# op-synth_0_83_bigger_mounting_holes.net
KiCad netlist of a schematic drawn in EAGLE
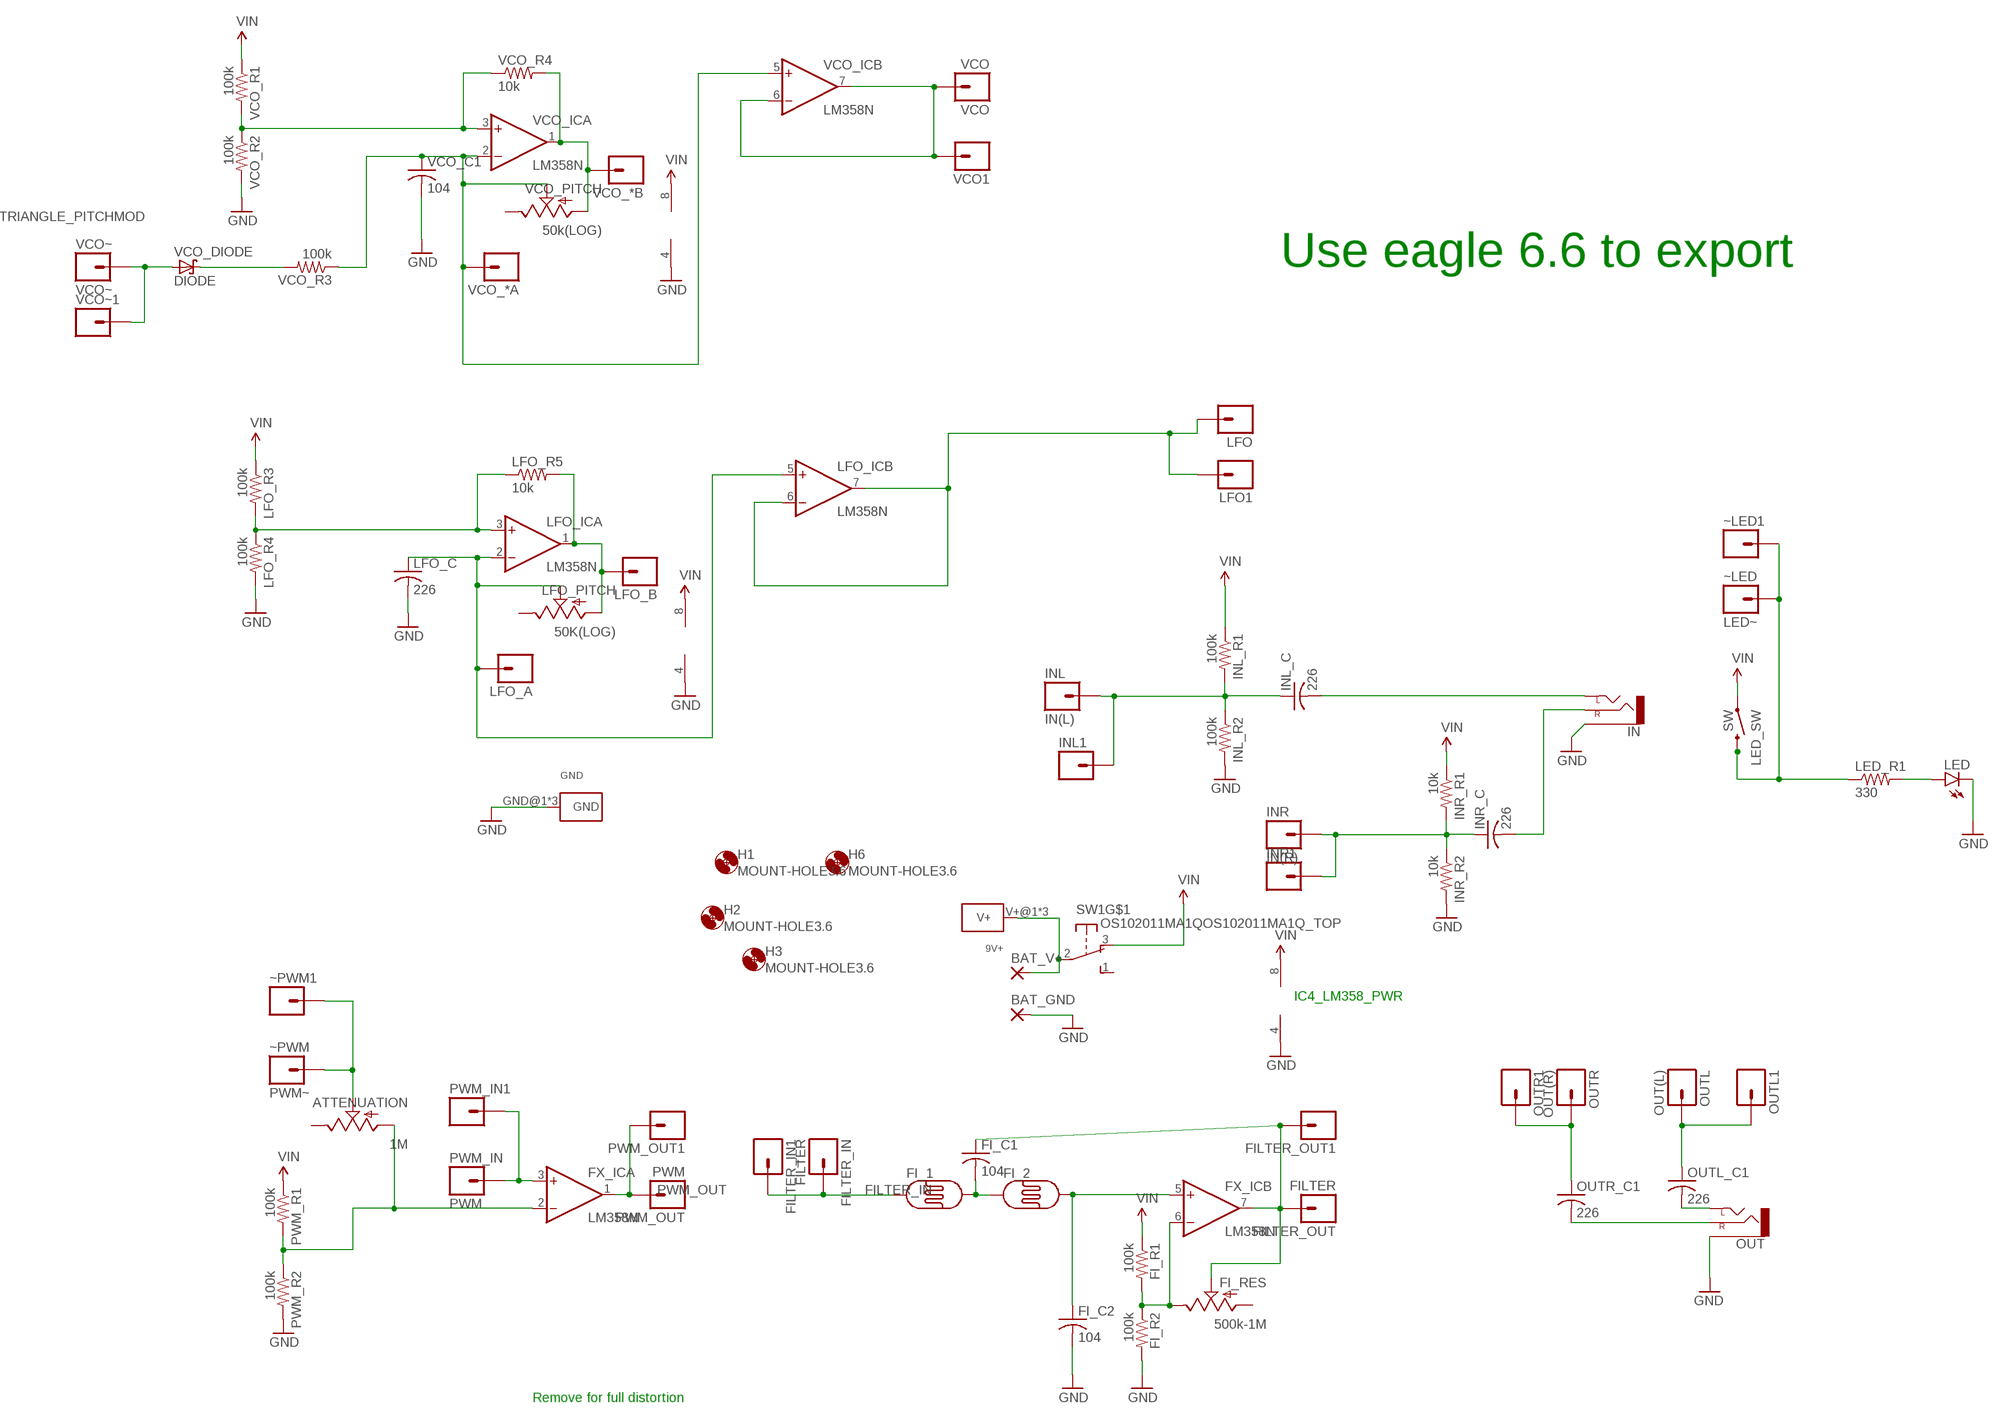
[diagram p0: schematic, sheet 1]

(export (version "E")
  (design (tool "Eeschema 10.0.6"))
  (components
    (comp (ref "9V+")
      (value "KEYSTONE-629+")
      (footprint "eagle-import:KEYSTONE_BATTAERY_TERMINAL-629+")
      (libsource (lib "eagle-import") (part "KEYSTONE-629+"))
    )
    (comp (ref "ATTENUATION")
      (value "1M")
      (footprint "eagle-import:TRIM_POT")
      (libsource (lib "eagle-import") (part "POTTRIM"))
    )
    (comp (ref "BAT_GND")
      (value "3,81/1,4")
      (footprint "eagle-import:3,81_1,4")
      (libsource (lib "eagle-import") (part "3,81/1,4"))
    )
    (comp (ref "BAT_V+")
      (value "3,81/1,4")
      (footprint "eagle-import:3,81_1,4")
      (libsource (lib "eagle-import") (part "3,81/1,4"))
    )
    (comp (ref "FILTER_IN")
      (value "FILTER")
      (footprint "eagle-import:1X01_SIDE_NAME")
      (libsource (lib "eagle-import") (part "HEADER-1X1"))
    )
    (comp (ref "FILTER_IN1")
      (value "HEADER-1X1")
      (footprint "eagle-import:1X01_SIDE_NAME")
      (libsource (lib "eagle-import") (part "HEADER-1X1"))
    )
    (comp (ref "FILTER_OUT")
      (value "FILTER")
      (footprint "eagle-import:1X01_SIDE_NAME")
      (libsource (lib "eagle-import") (part "HEADER-1X1"))
    )
    (comp (ref "FILTER_OUT1")
      (value "HEADER-1X1")
      (footprint "eagle-import:1X01_SIDE_NAME")
      (libsource (lib "eagle-import") (part "HEADER-1X1"))
    )
    (comp (ref "FI_1")
      (value "PHOTOCELLPTH")
      (footprint "eagle-import:PHOTOCELL")
      (libsource (lib "eagle-import") (part "PHOTOCELLPTH"))
    )
    (comp (ref "FI_2")
      (value "PHOTOCELLPTH")
      (footprint "eagle-import:PHOTOCELL")
      (libsource (lib "eagle-import") (part "PHOTOCELLPTH"))
    )
    (comp (ref "FI_C1")
      (value "104")
      (footprint "eagle-import:C050-024X044")
      (libsource (lib "eagle-import") (part "resistor_C-US050-024X044"))
    )
    (comp (ref "FI_C2")
      (value "104")
      (footprint "eagle-import:C050-024X044")
      (libsource (lib "eagle-import") (part "resistor_C-US050-024X044"))
    )
    (comp (ref "FI_R1")
      (value "100k")
      (footprint "eagle-import:0204_7")
      (libsource (lib "eagle-import") (part "R-US_0204/7"))
    )
    (comp (ref "FI_R2")
      (value "100k")
      (footprint "eagle-import:0204_7")
      (libsource (lib "eagle-import") (part "R-US_0204/7"))
    )
    (comp (ref "FI_RES")
      (value "500k-1M")
      (footprint "eagle-import:ALPS_POT")
      (libsource (lib "eagle-import") (part "POT"))
    )
    (comp (ref "FX_IC")
      (value "LM358N")
      (footprint "eagle-import:DIL08")
      (libsource (lib "eagle-import") (part "LM358N"))
    )
    (comp (ref "GND")
      (value "KEYSTONE-629")
      (footprint "eagle-import:KEYSTONE_AA_AAA_BATTERY_TERMINAL-629")
      (libsource (lib "eagle-import") (part "KEYSTONE-629"))
    )
    (comp (ref "H1")
      (value "MOUNT-HOLE3.6")
      (footprint "eagle-import:3,6")
      (libsource (lib "eagle-import") (part "MOUNT-HOLE3.6"))
    )
    (comp (ref "H2")
      (value "MOUNT-HOLE3.6")
      (footprint "eagle-import:3,6")
      (libsource (lib "eagle-import") (part "MOUNT-HOLE3.6"))
    )
    (comp (ref "H3")
      (value "MOUNT-HOLE3.6")
      (footprint "eagle-import:3,6")
      (libsource (lib "eagle-import") (part "MOUNT-HOLE3.6"))
    )
    (comp (ref "H6")
      (value "MOUNT-HOLE3.6")
      (footprint "eagle-import:3,6")
      (libsource (lib "eagle-import") (part "MOUNT-HOLE3.6"))
    )
    (comp (ref "IN")
      (value "AUDIO-JACKPTH")
      (footprint "eagle-import:AUDIO-JACK")
      (libsource (lib "eagle-import") (part "AUDIO-JACKPTH"))
    )
    (comp (ref "INL")
      (value "IN(L)")
      (footprint "eagle-import:1X01_SIDE_NAME")
      (libsource (lib "eagle-import") (part "HEADER-1X1"))
    )
    (comp (ref "INL1")
      (value "HEADER-1X1")
      (footprint "eagle-import:1X01_SIDE_NAME")
      (libsource (lib "eagle-import") (part "HEADER-1X1"))
    )
    (comp (ref "INL_C")
      (value "226")
      (footprint "eagle-import:C050-024X044")
      (libsource (lib "eagle-import") (part "C-US050-024X044"))
    )
    (comp (ref "INL_R1")
      (value "100k")
      (footprint "eagle-import:0204_7")
      (libsource (lib "eagle-import") (part "R-US_0204/7"))
    )
    (comp (ref "INL_R2")
      (value "100k")
      (footprint "eagle-import:0204_7")
      (libsource (lib "eagle-import") (part "R-US_0204/7"))
    )
    (comp (ref "INR")
      (value "IN(R)")
      (footprint "eagle-import:1X01_SIDE_NAME")
      (libsource (lib "eagle-import") (part "HEADER-1X1"))
    )
    (comp (ref "INR1")
      (value "HEADER-1X1")
      (footprint "eagle-import:1X01_SIDE_NAME")
      (libsource (lib "eagle-import") (part "HEADER-1X1"))
    )
    (comp (ref "INR_C")
      (value "226")
      (footprint "eagle-import:C050-024X044")
      (libsource (lib "eagle-import") (part "C-US050-024X044"))
    )
    (comp (ref "INR_R1")
      (value "10k")
      (footprint "eagle-import:0204_7")
      (libsource (lib "eagle-import") (part "R-US_0204/7"))
    )
    (comp (ref "INR_R2")
      (value "10k")
      (footprint "eagle-import:0204_7")
      (libsource (lib "eagle-import") (part "R-US_0204/7"))
    )
    (comp (ref "LED")
      (value "LED5MM")
      (footprint "eagle-import:LED5MM")
      (libsource (lib "eagle-import") (part "LED5MM"))
    )
    (comp (ref "LED_R1")
      (value "330")
      (footprint "eagle-import:0204_7")
      (libsource (lib "eagle-import") (part "R-US_0204/7"))
    )
    (comp (ref "LED_SW")
      (value "SW")
      (footprint "eagle-import:TACTILE-PTH-12MM")
      (libsource (lib "eagle-import") (part "SWITCH-MOMENTARY-212MM"))
    )
    (comp (ref "LFO")
      (value "HEADER-1X1")
      (footprint "eagle-import:1X01_SIDE_NAME")
      (libsource (lib "eagle-import") (part "HEADER-1X1"))
    )
    (comp (ref "LFO1")
      (value "HEADER-1X1")
      (footprint "eagle-import:1X01_SIDE_NAME")
      (libsource (lib "eagle-import") (part "HEADER-1X1"))
    )
    (comp (ref "LFO_A")
      (value "HEADER-1X1")
      (footprint "eagle-import:1X01_SIDE_NAME")
      (libsource (lib "eagle-import") (part "HEADER-1X1"))
    )
    (comp (ref "LFO_B")
      (value "HEADER-1X1")
      (footprint "eagle-import:1X01_SIDE_NAME")
      (libsource (lib "eagle-import") (part "HEADER-1X1"))
    )
    (comp (ref "LFO_C")
      (value "226")
      (footprint "eagle-import:C050-024X044")
      (libsource (lib "eagle-import") (part "resistor_C-US050-024X044"))
    )
    (comp (ref "LFO_IC")
      (value "LM358N")
      (footprint "eagle-import:DIL08")
      (libsource (lib "eagle-import") (part "LM358N"))
    )
    (comp (ref "LFO_PITCH")
      (value "50K(LOG)")
      (footprint "eagle-import:ALPS_POT")
      (libsource (lib "eagle-import") (part "POT"))
    )
    (comp (ref "LFO_R3")
      (value "100k")
      (footprint "eagle-import:0204_7")
      (libsource (lib "eagle-import") (part "R-US_0204/7"))
    )
    (comp (ref "LFO_R4")
      (value "100k")
      (footprint "eagle-import:0204_7")
      (libsource (lib "eagle-import") (part "R-US_0204/7"))
    )
    (comp (ref "LFO_R5")
      (value "10k")
      (footprint "eagle-import:0204_7")
      (libsource (lib "eagle-import") (part "R-US_0204/7"))
    )
    (comp (ref "OUT")
      (value "AUDIO-JACKPTH")
      (footprint "eagle-import:AUDIO-JACK")
      (libsource (lib "eagle-import") (part "AUDIO-JACKPTH"))
    )
    (comp (ref "OUTL")
      (value "OUT(L)")
      (footprint "eagle-import:1X01_SIDE_NAME")
      (libsource (lib "eagle-import") (part "HEADER-1X1"))
    )
    (comp (ref "OUTL1")
      (value "HEADER-1X1")
      (footprint "eagle-import:1X01_SIDE_NAME")
      (libsource (lib "eagle-import") (part "HEADER-1X1"))
    )
    (comp (ref "OUTL_C1")
      (value "226")
      (footprint "eagle-import:C050-024X044")
      (libsource (lib "eagle-import") (part "C-US050-024X044"))
    )
    (comp (ref "OUTR")
      (value "OUT(R)")
      (footprint "eagle-import:1X01_SIDE_NAME")
      (libsource (lib "eagle-import") (part "HEADER-1X1"))
    )
    (comp (ref "OUTR1")
      (value "HEADER-1X1")
      (footprint "eagle-import:1X01_SIDE_NAME")
      (libsource (lib "eagle-import") (part "HEADER-1X1"))
    )
    (comp (ref "OUTR_C1")
      (value "226")
      (footprint "eagle-import:C050-024X044")
      (libsource (lib "eagle-import") (part "C-US050-024X044"))
    )
    (comp (ref "PWM_IN")
      (value "PWM")
      (footprint "eagle-import:1X01_SIDE_NAME")
      (libsource (lib "eagle-import") (part "HEADER-1X1"))
    )
    (comp (ref "PWM_IN1")
      (value "HEADER-1X1")
      (footprint "eagle-import:1X01_SIDE_NAME")
      (libsource (lib "eagle-import") (part "HEADER-1X1"))
    )
    (comp (ref "PWM_OUT")
      (value "PWM")
      (footprint "eagle-import:1X01_SIDE_NAME")
      (libsource (lib "eagle-import") (part "HEADER-1X1"))
    )
    (comp (ref "PWM_OUT1")
      (value "HEADER-1X1")
      (footprint "eagle-import:1X01_SIDE_NAME")
      (libsource (lib "eagle-import") (part "HEADER-1X1"))
    )
    (comp (ref "PWM_R1")
      (value "100k")
      (footprint "eagle-import:0204_7")
      (libsource (lib "eagle-import") (part "R-US_0204/7"))
    )
    (comp (ref "PWM_R2")
      (value "100k")
      (footprint "eagle-import:0204_7")
      (libsource (lib "eagle-import") (part "R-US_0204/7"))
    )
    (comp (ref "SW1")
      (value "OS102011MA1QOS102011MA1Q_TOP")
      (footprint "eagle-import:OS102011MA1Q")
      (libsource (lib "eagle-import") (part "OS102011MA1QOS102011MA1Q_TOP"))
    )
    (comp (ref "VCO")
      (value "VCO")
      (footprint "eagle-import:1X01_SIDE_NAME")
      (libsource (lib "eagle-import") (part "HEADER-1X1"))
    )
    (comp (ref "VCO1")
      (value "HEADER-1X1")
      (footprint "eagle-import:1X01_SIDE_NAME")
      (libsource (lib "eagle-import") (part "HEADER-1X1"))
    )
    (comp (ref "VCO_*A")
      (value "HEADER-1X1")
      (footprint "eagle-import:1X01_SIDE_NAME")
      (libsource (lib "eagle-import") (part "HEADER-1X1"))
    )
    (comp (ref "VCO_*B")
      (value "HEADER-1X1")
      (footprint "eagle-import:1X01_SIDE_NAME")
      (libsource (lib "eagle-import") (part "HEADER-1X1"))
    )
    (comp (ref "VCO_C1")
      (value "104")
      (footprint "eagle-import:C050-024X044")
      (libsource (lib "eagle-import") (part "C-US050-024X044"))
    )
    (comp (ref "VCO_DIODE")
      (value "DIODE")
      (footprint "eagle-import:DO41-7")
      (libsource (lib "eagle-import") (part "SCHOTTKY-DIODEDO41-7"))
    )
    (comp (ref "VCO_IC")
      (value "LM358N")
      (footprint "eagle-import:DIL08")
      (libsource (lib "eagle-import") (part "LM358N"))
    )
    (comp (ref "VCO_PITCH")
      (value "50k(LOG)")
      (footprint "eagle-import:ALPS_POT")
      (libsource (lib "eagle-import") (part "POT"))
    )
    (comp (ref "VCO_R1")
      (value "100k")
      (footprint "eagle-import:0204_7")
      (libsource (lib "eagle-import") (part "R-US_0204/7"))
    )
    (comp (ref "VCO_R2")
      (value "100k")
      (footprint "eagle-import:0204_7")
      (libsource (lib "eagle-import") (part "R-US_0204/7"))
    )
    (comp (ref "VCO_R3")
      (value "100k")
      (footprint "eagle-import:0204_7")
      (libsource (lib "eagle-import") (part "R-US_0204/7"))
    )
    (comp (ref "VCO_R4")
      (value "10k")
      (footprint "eagle-import:0204_7")
      (libsource (lib "eagle-import") (part "R-US_0204/7"))
    )
    (comp (ref "VCO~")
      (value "VCO~")
      (footprint "eagle-import:1X01_SIDE_NAME")
      (libsource (lib "eagle-import") (part "HEADER-1X1"))
    )
    (comp (ref "VCO~1")
      (value "HEADER-1X1")
      (footprint "eagle-import:1X01_SIDE_NAME")
      (libsource (lib "eagle-import") (part "HEADER-1X1"))
    )
    (comp (ref "~LED")
      (value "LED~")
      (footprint "eagle-import:1X01_SIDE_NAME")
      (libsource (lib "eagle-import") (part "HEADER-1X1"))
    )
    (comp (ref "~LED1")
      (value "HEADER-1X1")
      (footprint "eagle-import:1X01_SIDE_NAME")
      (libsource (lib "eagle-import") (part "HEADER-1X1"))
    )
    (comp (ref "~PWM")
      (value "PWM~")
      (footprint "eagle-import:1X01_SIDE_NAME")
      (libsource (lib "eagle-import") (part "HEADER-1X1"))
    )
    (comp (ref "~PWM1")
      (value "HEADER-1X1")
      (footprint "eagle-import:1X01_SIDE_NAME")
      (libsource (lib "eagle-import") (part "HEADER-1X1"))
    )
  )
  (nets
    (net (code "1") (name "/FILTER_IN") (class "Default")
      (node (ref "FILTER_IN") (pin "1") (pinfunction "1_1") (pintype "passive"))
      (node (ref "FILTER_IN1") (pin "1") (pinfunction "1_1") (pintype "passive"))
      (node (ref "FI_1") (pin "1") (pinfunction "P$1_1") (pintype "bidirectional"))
    )
    (net (code "2") (name "/PWM_OUT") (class "Default")
      (node (ref "FX_IC") (pin "1") (pinfunction "OUT_1") (pintype "output"))
      (node (ref "PWM_OUT") (pin "1") (pinfunction "1_1") (pintype "passive"))
      (node (ref "PWM_OUT1") (pin "1") (pinfunction "1_1") (pintype "passive"))
    )
    (net (code "3") (name "/TRIANGLE_PITCHMOD") (class "Default")
      (node (ref "VCO_DIODE") (pin "A") (pinfunction "A_A") (pintype "passive"))
      (node (ref "VCO~") (pin "1") (pinfunction "1_1") (pintype "passive"))
      (node (ref "VCO~1") (pin "1") (pinfunction "1_1") (pintype "passive"))
    )
    (net (code "4") (name "GND") (class "Default")
      (node (ref "BAT_GND") (pin "1") (pinfunction "P_1") (pintype "passive"))
      (node (ref "FI_C2") (pin "2") (pinfunction "2_2") (pintype "passive"))
      (node (ref "FI_R2") (pin "2") (pinfunction "2_2") (pintype "passive"))
      (node (ref "FX_IC") (pin "4") (pinfunction "V-_4") (pintype "power_in"))
      (node (ref "GND") (pin "GND@1") (pinfunction "GND_GND@1") (pintype "power_in"))
      (node (ref "GND") (pin "GND@2") (pinfunction "GND_GND@2") (pintype "power_in"))
      (node (ref "GND") (pin "GND@3") (pinfunction "GND_GND@3") (pintype "power_in"))
      (node (ref "IN") (pin "SLEEVE") (pinfunction "SLEEVE_SLEEVE") (pintype "bidirectional"))
      (node (ref "INL_R2") (pin "2") (pinfunction "2_2") (pintype "passive"))
      (node (ref "INR_R2") (pin "2") (pinfunction "2_2") (pintype "passive"))
      (node (ref "LED") (pin "K") (pinfunction "C_K") (pintype "passive"))
      (node (ref "LFO_C") (pin "2") (pinfunction "2_2") (pintype "passive"))
      (node (ref "LFO_IC") (pin "4") (pinfunction "V-_4") (pintype "power_in"))
      (node (ref "LFO_R4") (pin "2") (pinfunction "2_2") (pintype "passive"))
      (node (ref "OUT") (pin "SLEEVE") (pinfunction "SLEEVE_SLEEVE") (pintype "bidirectional"))
      (node (ref "PWM_R2") (pin "2") (pinfunction "2_2") (pintype "passive"))
      (node (ref "VCO_C1") (pin "2") (pinfunction "2_2") (pintype "passive"))
      (node (ref "VCO_IC") (pin "4") (pinfunction "V-_4") (pintype "power_in"))
      (node (ref "VCO_R2") (pin "2") (pinfunction "2_2") (pintype "passive"))
    )
    (net (code "5") (name "Net-(ATTENUATION-A)") (class "Default")
      (node (ref "ATTENUATION") (pin "3") (pinfunction "A_3") (pintype "passive"))
      (node (ref "FX_IC") (pin "2") (pinfunction "-IN_2") (pintype "input"))
      (node (ref "PWM_R1") (pin "2") (pinfunction "2_2") (pintype "passive"))
      (node (ref "PWM_R2") (pin "1") (pinfunction "1_1") (pintype "passive"))
    )
    (net (code "6") (name "Net-(ATTENUATION-S)") (class "Default")
      (node (ref "ATTENUATION") (pin "1") (pinfunction "S_1") (pintype "passive"))
      (node (ref "~PWM") (pin "1") (pinfunction "1_1") (pintype "passive"))
      (node (ref "~PWM1") (pin "1") (pinfunction "1_1") (pintype "passive"))
    )
    (net (code "7") (name "Net-(BAT_V+-P)") (class "Default")
      (node (ref "9V+") (pin "V+@1") (pinfunction "V+_V+@1") (pintype "power_in"))
      (node (ref "9V+") (pin "V+@2") (pinfunction "V+_V+@2") (pintype "power_in"))
      (node (ref "9V+") (pin "V+@3") (pinfunction "V+_V+@3") (pintype "power_in"))
      (node (ref "BAT_V+") (pin "1") (pinfunction "P_1") (pintype "passive"))
      (node (ref "SW1") (pin "2") (pinfunction "P_2") (pintype "passive"))
    )
    (net (code "8") (name "Net-(FI_1-P$2)") (class "Default")
      (node (ref "FI_1") (pin "2") (pinfunction "P$2_2") (pintype "bidirectional"))
      (node (ref "FI_2") (pin "1") (pinfunction "P$1_1") (pintype "bidirectional"))
      (node (ref "FI_C1") (pin "2") (pinfunction "2_2") (pintype "passive"))
    )
    (net (code "9") (name "Net-(FI_2-P$2)") (class "Default")
      (node (ref "FI_2") (pin "2") (pinfunction "P$2_2") (pintype "bidirectional"))
      (node (ref "FI_C2") (pin "1") (pinfunction "1_1") (pintype "passive"))
      (node (ref "FX_IC") (pin "5") (pinfunction "+IN_5") (pintype "input"))
    )
    (net (code "10") (name "Net-(FI_RES-E)") (class "Default")
      (node (ref "FI_R1") (pin "2") (pinfunction "2_2") (pintype "passive"))
      (node (ref "FI_R2") (pin "1") (pinfunction "1_1") (pintype "passive"))
      (node (ref "FI_RES") (pin "P$1") (pinfunction "E_P$1") (pintype "passive"))
      (node (ref "FX_IC") (pin "6") (pinfunction "-IN_6") (pintype "input"))
    )
    (net (code "11") (name "Net-(FI_RES-S)") (class "Default")
      (node (ref "FILTER_OUT") (pin "1") (pinfunction "1_1") (pintype "passive"))
      (node (ref "FILTER_OUT1") (pin "1") (pinfunction "1_1") (pintype "passive"))
      (node (ref "FI_C1") (pin "1") (pinfunction "1_1") (pintype "passive"))
      (node (ref "FI_RES") (pin "P$2") (pinfunction "S_P$2") (pintype "passive"))
      (node (ref "FX_IC") (pin "7") (pinfunction "OUT_7") (pintype "output"))
    )
    (net (code "12") (name "Net-(FX_ICA-+IN)") (class "Default")
      (node (ref "FX_IC") (pin "3") (pinfunction "+IN_3") (pintype "input"))
      (node (ref "PWM_IN") (pin "1") (pinfunction "1_1") (pintype "passive"))
      (node (ref "PWM_IN1") (pin "1") (pinfunction "1_1") (pintype "passive"))
    )
    (net (code "13") (name "Net-(IN-LEFT)") (class "Default")
      (node (ref "IN") (pin "TIP") (pinfunction "LEFT_TIP") (pintype "bidirectional"))
      (node (ref "INL_C") (pin "2") (pinfunction "2_2") (pintype "passive"))
    )
    (net (code "14") (name "Net-(IN-RIGHT)") (class "Default")
      (node (ref "IN") (pin "RING") (pinfunction "RIGHT_RING") (pintype "bidirectional"))
      (node (ref "INR_C") (pin "2") (pinfunction "2_2") (pintype "passive"))
    )
    (net (code "15") (name "Net-(INL-Pad1)") (class "Default")
      (node (ref "INL") (pin "1") (pinfunction "1_1") (pintype "passive"))
      (node (ref "INL1") (pin "1") (pinfunction "1_1") (pintype "passive"))
      (node (ref "INL_C") (pin "1") (pinfunction "1_1") (pintype "passive"))
      (node (ref "INL_R1") (pin "2") (pinfunction "2_2") (pintype "passive"))
      (node (ref "INL_R2") (pin "1") (pinfunction "1_1") (pintype "passive"))
    )
    (net (code "16") (name "Net-(INR-Pad1)") (class "Default")
      (node (ref "INR") (pin "1") (pinfunction "1_1") (pintype "passive"))
      (node (ref "INR1") (pin "1") (pinfunction "1_1") (pintype "passive"))
      (node (ref "INR_C") (pin "1") (pinfunction "1_1") (pintype "passive"))
      (node (ref "INR_R1") (pin "2") (pinfunction "2_2") (pintype "passive"))
      (node (ref "INR_R2") (pin "1") (pinfunction "1_1") (pintype "passive"))
    )
    (net (code "17") (name "Net-(LED-PadA)") (class "Default")
      (node (ref "LED") (pin "A") (pinfunction "A_A") (pintype "passive"))
      (node (ref "LED_R1") (pin "2") (pinfunction "2_2") (pintype "passive"))
    )
    (net (code "18") (name "Net-(LED_SW-2)") (class "Default")
      (node (ref "LED_R1") (pin "1") (pinfunction "1_1") (pintype "passive"))
      (node (ref "LED_SW") (pin "3") (pinfunction "2_3") (pintype "passive"))
      (node (ref "~LED") (pin "1") (pinfunction "1_1") (pintype "passive"))
      (node (ref "~LED1") (pin "1") (pinfunction "1_1") (pintype "passive"))
    )
    (net (code "19") (name "Net-(LFO_ICA-+IN)") (class "Default")
      (node (ref "LFO_IC") (pin "3") (pinfunction "+IN_3") (pintype "input"))
      (node (ref "LFO_R3") (pin "2") (pinfunction "2_2") (pintype "passive"))
      (node (ref "LFO_R4") (pin "1") (pinfunction "1_1") (pintype "passive"))
      (node (ref "LFO_R5") (pin "1") (pinfunction "1_1") (pintype "passive"))
    )
    (net (code "20") (name "Net-(LFO_ICA--IN)") (class "Default")
      (node (ref "LFO_A") (pin "1") (pinfunction "1_1") (pintype "passive"))
      (node (ref "LFO_C") (pin "1") (pinfunction "1_1") (pintype "passive"))
      (node (ref "LFO_IC") (pin "2") (pinfunction "-IN_2") (pintype "input"))
      (node (ref "LFO_IC") (pin "5") (pinfunction "+IN_5") (pintype "input"))
      (node (ref "LFO_PITCH") (pin "P$2") (pinfunction "S_P$2") (pintype "passive"))
    )
    (net (code "21") (name "Net-(LFO_ICA-OUT)") (class "Default")
      (node (ref "LFO_B") (pin "1") (pinfunction "1_1") (pintype "passive"))
      (node (ref "LFO_IC") (pin "1") (pinfunction "OUT_1") (pintype "output"))
      (node (ref "LFO_PITCH") (pin "P$3") (pinfunction "A_P$3") (pintype "passive"))
      (node (ref "LFO_R5") (pin "2") (pinfunction "2_2") (pintype "passive"))
    )
    (net (code "22") (name "Net-(LFO_ICB--IN)") (class "Default")
      (node (ref "LFO") (pin "1") (pinfunction "1_1") (pintype "passive"))
      (node (ref "LFO1") (pin "1") (pinfunction "1_1") (pintype "passive"))
      (node (ref "LFO_IC") (pin "6") (pinfunction "-IN_6") (pintype "input"))
      (node (ref "LFO_IC") (pin "7") (pinfunction "OUT_7") (pintype "output"))
    )
    (net (code "23") (name "Net-(OUT-LEFT)") (class "Default")
      (node (ref "OUT") (pin "TIP") (pinfunction "LEFT_TIP") (pintype "bidirectional"))
      (node (ref "OUTL_C1") (pin "2") (pinfunction "2_2") (pintype "passive"))
    )
    (net (code "24") (name "Net-(OUT-RIGHT)") (class "Default")
      (node (ref "OUT") (pin "RING") (pinfunction "RIGHT_RING") (pintype "bidirectional"))
      (node (ref "OUTR_C1") (pin "2") (pinfunction "2_2") (pintype "passive"))
    )
    (net (code "25") (name "Net-(OUTL-Pad1)") (class "Default")
      (node (ref "OUTL") (pin "1") (pinfunction "1_1") (pintype "passive"))
      (node (ref "OUTL1") (pin "1") (pinfunction "1_1") (pintype "passive"))
      (node (ref "OUTL_C1") (pin "1") (pinfunction "1_1") (pintype "passive"))
    )
    (net (code "26") (name "Net-(OUTR-Pad1)") (class "Default")
      (node (ref "OUTR") (pin "1") (pinfunction "1_1") (pintype "passive"))
      (node (ref "OUTR1") (pin "1") (pinfunction "1_1") (pintype "passive"))
      (node (ref "OUTR_C1") (pin "1") (pinfunction "1_1") (pintype "passive"))
    )
    (net (code "27") (name "Net-(VCO_DIODE-PadC)") (class "Default")
      (node (ref "VCO_DIODE") (pin "C") (pinfunction "C_C") (pintype "passive"))
      (node (ref "VCO_R3") (pin "2") (pinfunction "2_2") (pintype "passive"))
    )
    (net (code "28") (name "Net-(VCO_ICA-+IN)") (class "Default")
      (node (ref "VCO_IC") (pin "3") (pinfunction "+IN_3") (pintype "input"))
      (node (ref "VCO_R1") (pin "2") (pinfunction "2_2") (pintype "passive"))
      (node (ref "VCO_R2") (pin "1") (pinfunction "1_1") (pintype "passive"))
      (node (ref "VCO_R4") (pin "1") (pinfunction "1_1") (pintype "passive"))
    )
    (net (code "29") (name "Net-(VCO_ICA--IN)") (class "Default")
      (node (ref "VCO_*A") (pin "1") (pinfunction "1_1") (pintype "passive"))
      (node (ref "VCO_C1") (pin "1") (pinfunction "1_1") (pintype "passive"))
      (node (ref "VCO_IC") (pin "2") (pinfunction "-IN_2") (pintype "input"))
      (node (ref "VCO_IC") (pin "5") (pinfunction "+IN_5") (pintype "input"))
      (node (ref "VCO_PITCH") (pin "P$2") (pinfunction "S_P$2") (pintype "passive"))
      (node (ref "VCO_R3") (pin "1") (pinfunction "1_1") (pintype "passive"))
    )
    (net (code "30") (name "Net-(VCO_ICA-OUT)") (class "Default")
      (node (ref "VCO_*B") (pin "1") (pinfunction "1_1") (pintype "passive"))
      (node (ref "VCO_IC") (pin "1") (pinfunction "OUT_1") (pintype "output"))
      (node (ref "VCO_PITCH") (pin "P$3") (pinfunction "A_P$3") (pintype "passive"))
      (node (ref "VCO_R4") (pin "2") (pinfunction "2_2") (pintype "passive"))
    )
    (net (code "31") (name "Net-(VCO_ICB--IN)") (class "Default")
      (node (ref "VCO") (pin "1") (pinfunction "1_1") (pintype "passive"))
      (node (ref "VCO1") (pin "1") (pinfunction "1_1") (pintype "passive"))
      (node (ref "VCO_IC") (pin "6") (pinfunction "-IN_6") (pintype "input"))
      (node (ref "VCO_IC") (pin "7") (pinfunction "OUT_7") (pintype "output"))
    )
    (net (code "32") (name "VIN") (class "Default")
      (node (ref "FI_R1") (pin "1") (pinfunction "1_1") (pintype "passive"))
      (node (ref "FX_IC") (pin "8") (pinfunction "V+_8") (pintype "power_in"))
      (node (ref "INL_R1") (pin "1") (pinfunction "1_1") (pintype "passive"))
      (node (ref "INR_R1") (pin "1") (pinfunction "1_1") (pintype "passive"))
      (node (ref "LED_SW") (pin "1") (pinfunction "1_1") (pintype "passive"))
      (node (ref "LFO_IC") (pin "8") (pinfunction "V+_8") (pintype "power_in"))
      (node (ref "LFO_R3") (pin "1") (pinfunction "1_1") (pintype "passive"))
      (node (ref "PWM_R1") (pin "1") (pinfunction "1_1") (pintype "passive"))
      (node (ref "SW1") (pin "3") (pinfunction "O_3") (pintype "passive"))
      (node (ref "VCO_IC") (pin "8") (pinfunction "V+_8") (pintype "power_in"))
      (node (ref "VCO_R1") (pin "1") (pinfunction "1_1") (pintype "passive"))
    )
    (net (code "33") (name "unconnected-(ATTENUATION-E-Pad2)") (class "Default")
      (node (ref "ATTENUATION") (pin "2") (pinfunction "E_2") (pintype "passive"))
    )
    (net (code "34") (name "unconnected-(FI_RES-A-PadP$3)") (class "Default")
      (node (ref "FI_RES") (pin "P$3") (pinfunction "A_P$3") (pintype "passive"))
    )
    (net (code "35") (name "unconnected-(LFO_PITCH-E-PadP$1)") (class "Default")
      (node (ref "LFO_PITCH") (pin "P$1") (pinfunction "E_P$1") (pintype "passive"))
    )
    (net (code "36") (name "unconnected-(SW1A-S-Pad1)") (class "Default")
      (node (ref "SW1") (pin "1") (pinfunction "S_1") (pintype "passive"))
    )
    (net (code "37") (name "unconnected-(VCO_PITCH-E-PadP$1)") (class "Default")
      (node (ref "VCO_PITCH") (pin "P$1") (pinfunction "E_P$1") (pintype "passive"))
    )
  )
)
